# ui_front.net
KiCad netlist of a schematic drawn in Altium Designer
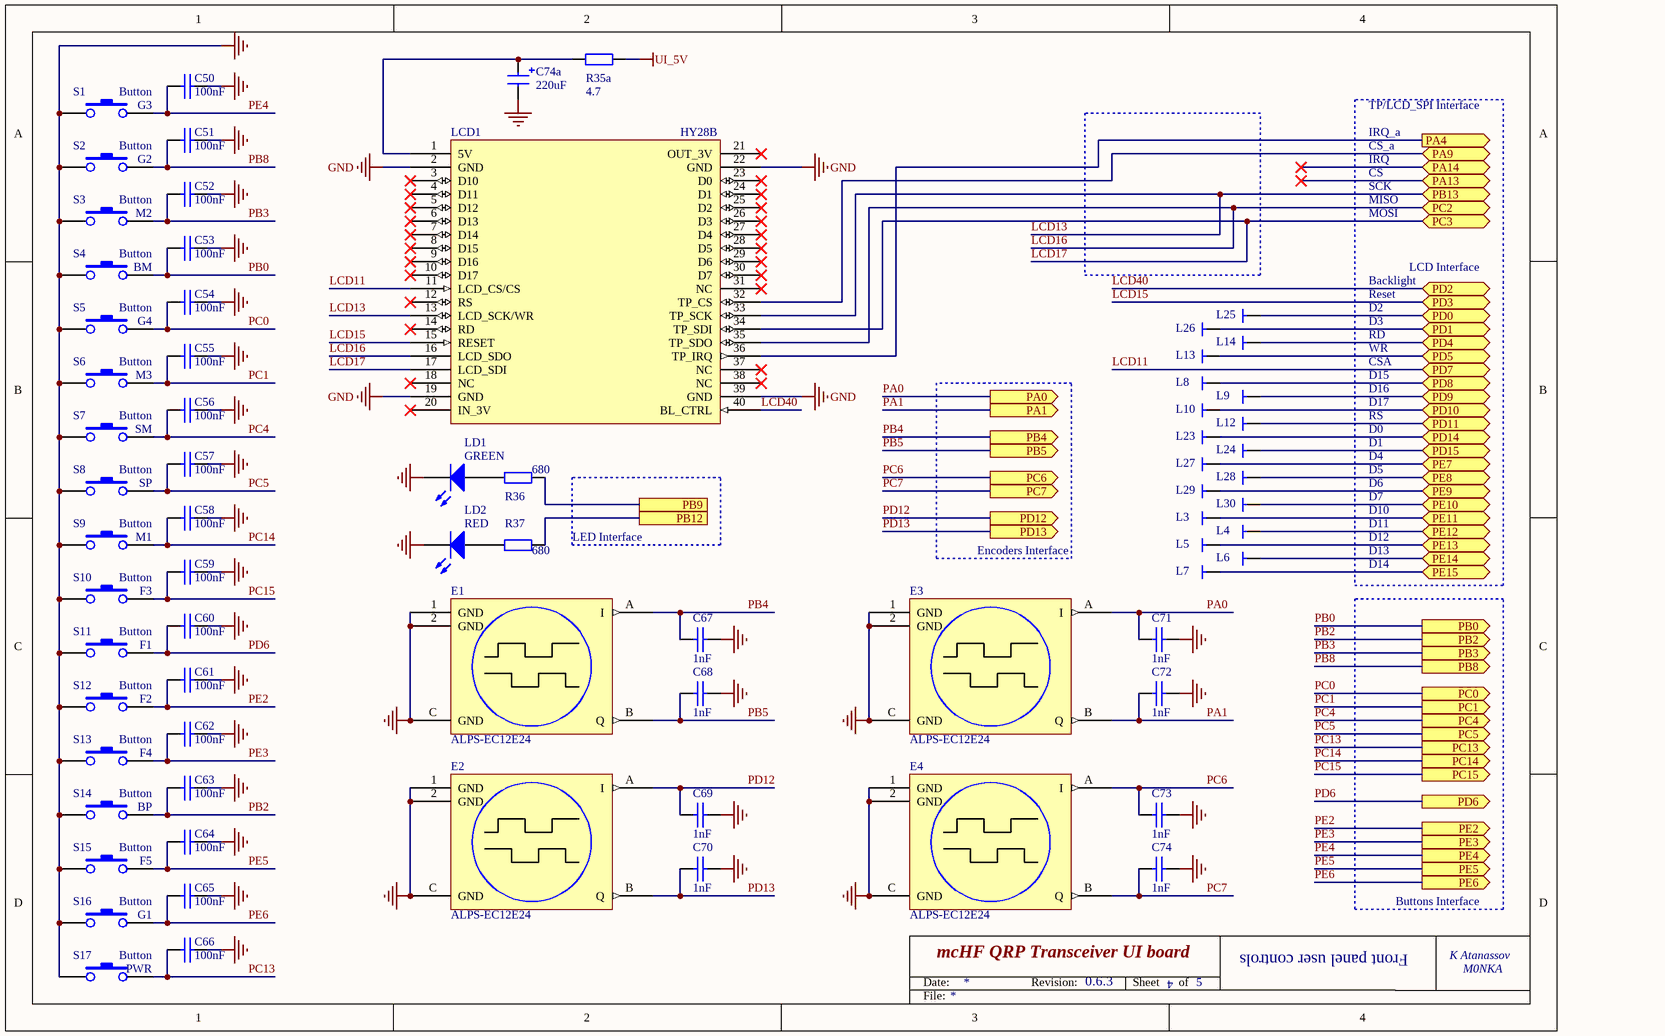
[diagram p0: ui_front.SchDoc]

(export (version "E")
  (design (tool "Eeschema 10.0.6"))
  (components
    (comp (ref "C50")
      (value "100nF")
      (footprint "0805-Pro")
      (description "Capacitor")
      (libsource (lib "mcHF_ui") (part "CAP"))
    )
    (comp (ref "C51")
      (value "100nF")
      (footprint "0805-Pro")
      (description "Capacitor")
      (libsource (lib "mcHF_ui") (part "CAP"))
    )
    (comp (ref "C52")
      (value "100nF")
      (footprint "0805-Pro")
      (description "Capacitor")
      (libsource (lib "mcHF_ui") (part "CAP"))
    )
    (comp (ref "C53")
      (value "100nF")
      (footprint "0805-Pro")
      (description "Capacitor")
      (libsource (lib "mcHF_ui") (part "CAP"))
    )
    (comp (ref "C54")
      (value "100nF")
      (footprint "0805-Pro")
      (description "Capacitor")
      (libsource (lib "mcHF_ui") (part "CAP"))
    )
    (comp (ref "C55")
      (value "100nF")
      (footprint "0805-Pro")
      (description "Capacitor")
      (libsource (lib "mcHF_ui") (part "CAP"))
    )
    (comp (ref "C56")
      (value "100nF")
      (footprint "0805-Pro")
      (description "Capacitor")
      (libsource (lib "mcHF_ui") (part "CAP"))
    )
    (comp (ref "C57")
      (value "100nF")
      (footprint "0805-Pro")
      (description "Capacitor")
      (libsource (lib "mcHF_ui") (part "CAP"))
    )
    (comp (ref "C58")
      (value "100nF")
      (footprint "0805-Pro")
      (description "Capacitor")
      (libsource (lib "mcHF_ui") (part "CAP"))
    )
    (comp (ref "C59")
      (value "100nF")
      (footprint "0805-Pro")
      (description "Capacitor")
      (libsource (lib "mcHF_ui") (part "CAP"))
    )
    (comp (ref "C60")
      (value "100nF")
      (footprint "0805-Pro")
      (description "Capacitor")
      (libsource (lib "mcHF_ui") (part "CAP"))
    )
    (comp (ref "C61")
      (value "100nF")
      (footprint "0805-Pro")
      (description "Capacitor")
      (libsource (lib "mcHF_ui") (part "CAP"))
    )
    (comp (ref "C62")
      (value "100nF")
      (footprint "0805-Pro")
      (description "Capacitor")
      (libsource (lib "mcHF_ui") (part "CAP"))
    )
    (comp (ref "C63")
      (value "100nF")
      (footprint "0805-Pro")
      (description "Capacitor")
      (libsource (lib "mcHF_ui") (part "CAP"))
    )
    (comp (ref "C64")
      (value "100nF")
      (footprint "0805-Pro")
      (description "Capacitor")
      (libsource (lib "mcHF_ui") (part "CAP"))
    )
    (comp (ref "C65")
      (value "100nF")
      (footprint "0805-Pro")
      (description "Capacitor")
      (libsource (lib "mcHF_ui") (part "CAP"))
    )
    (comp (ref "C66")
      (value "100nF")
      (footprint "0805-Pro")
      (description "Capacitor")
      (libsource (lib "mcHF_ui") (part "CAP"))
    )
    (comp (ref "C67")
      (value "1nF")
      (footprint "0805-Pro")
      (description "Capacitor")
      (libsource (lib "mcHF_ui") (part "CAP"))
    )
    (comp (ref "C68")
      (value "1nF")
      (footprint "0805-Pro")
      (description "Capacitor")
      (libsource (lib "mcHF_ui") (part "CAP"))
    )
    (comp (ref "C69")
      (value "1nF")
      (footprint "0805-Pro")
      (description "Capacitor")
      (libsource (lib "mcHF_ui") (part "CAP"))
    )
    (comp (ref "C70")
      (value "1nF")
      (footprint "0805-Pro")
      (description "Capacitor")
      (libsource (lib "mcHF_ui") (part "CAP"))
    )
    (comp (ref "C71")
      (value "1nF")
      (footprint "0805-Pro")
      (description "Capacitor")
      (libsource (lib "mcHF_ui") (part "CAP"))
    )
    (comp (ref "C72")
      (value "1nF")
      (footprint "0805-Pro")
      (description "Capacitor")
      (libsource (lib "mcHF_ui") (part "CAP"))
    )
    (comp (ref "C73")
      (value "1nF")
      (footprint "0805-Pro")
      (description "Capacitor")
      (libsource (lib "mcHF_ui") (part "CAP"))
    )
    (comp (ref "C74")
      (value "1nF")
      (footprint "0805-Pro")
      (description "Capacitor")
      (libsource (lib "mcHF_ui") (part "CAP"))
    )
    (comp (ref "C74a")
      (value "220uF")
      (footprint "CAP_ALUM")
      (description "Electrolitic capacitor")
      (libsource (lib "mcHF_ui") (part "CAP-POL"))
    )
    (comp (ref "E1")
      (value "ALPS-EC12E24")
      (footprint "Encoder")
      (description "ALPS Rotary Encoder")
      (libsource (lib "mcHF_ui") (part "Encoder"))
    )
    (comp (ref "E2")
      (value "ALPS-EC12E24")
      (footprint "Encoder")
      (description "ALPS Rotary Encoder")
      (libsource (lib "mcHF_ui") (part "Encoder"))
    )
    (comp (ref "E3")
      (value "ALPS-EC12E24")
      (footprint "Encoder")
      (description "ALPS Rotary Encoder")
      (libsource (lib "mcHF_ui") (part "Encoder"))
    )
    (comp (ref "E4")
      (value "ALPS-EC12E24")
      (footprint "Encoder")
      (description "ALPS Rotary Encoder")
      (libsource (lib "mcHF_ui") (part "Encoder"))
    )
    (comp (ref "L3")
      (value "TP")
      (footprint "tp")
      (description "Test point")
      (libsource (lib "mcHF_ui_b") (part "TP"))
    )
    (comp (ref "L4")
      (value "TP")
      (footprint "tp")
      (description "Test point")
      (libsource (lib "mcHF_ui_b") (part "TP"))
    )
    (comp (ref "L5")
      (value "TP")
      (footprint "tp")
      (description "Test point")
      (libsource (lib "mcHF_ui_b") (part "TP"))
    )
    (comp (ref "L6")
      (value "TP")
      (footprint "tp")
      (description "Test point")
      (libsource (lib "mcHF_ui_b") (part "TP"))
    )
    (comp (ref "L7")
      (value "TP")
      (footprint "tp")
      (description "Test point")
      (libsource (lib "mcHF_ui_b") (part "TP"))
    )
    (comp (ref "L8")
      (value "TP")
      (footprint "tp")
      (description "Test point")
      (libsource (lib "mcHF_ui_b") (part "TP"))
    )
    (comp (ref "L9")
      (value "TP")
      (footprint "tp")
      (description "Test point")
      (libsource (lib "mcHF_ui_b") (part "TP"))
    )
    (comp (ref "L10")
      (value "TP")
      (footprint "tp")
      (description "Test point")
      (libsource (lib "mcHF_ui_b") (part "TP"))
    )
    (comp (ref "L12")
      (value "TP")
      (footprint "tp")
      (description "Test point")
      (libsource (lib "mcHF_ui_b") (part "TP"))
    )
    (comp (ref "L13")
      (value "TP")
      (footprint "tp")
      (description "Test point")
      (libsource (lib "mcHF_ui_b") (part "TP"))
    )
    (comp (ref "L14")
      (value "TP")
      (footprint "tp")
      (description "Test point")
      (libsource (lib "mcHF_ui_b") (part "TP"))
    )
    (comp (ref "L23")
      (value "TP")
      (footprint "tp")
      (description "Test point")
      (libsource (lib "mcHF_ui_b") (part "TP"))
    )
    (comp (ref "L24")
      (value "TP")
      (footprint "tp")
      (description "Test point")
      (libsource (lib "mcHF_ui_b") (part "TP"))
    )
    (comp (ref "L25")
      (value "TP")
      (footprint "tp")
      (description "Test point")
      (libsource (lib "mcHF_ui_b") (part "TP"))
    )
    (comp (ref "L26")
      (value "TP")
      (footprint "tp")
      (description "Test point")
      (libsource (lib "mcHF_ui_b") (part "TP"))
    )
    (comp (ref "L27")
      (value "TP")
      (footprint "tp")
      (description "Test point")
      (libsource (lib "mcHF_ui_b") (part "TP"))
    )
    (comp (ref "L28")
      (value "TP")
      (footprint "tp")
      (description "Test point")
      (libsource (lib "mcHF_ui_b") (part "TP"))
    )
    (comp (ref "L29")
      (value "TP")
      (footprint "tp")
      (description "Test point")
      (libsource (lib "mcHF_ui_b") (part "TP"))
    )
    (comp (ref "L30")
      (value "TP")
      (footprint "tp")
      (description "Test point")
      (libsource (lib "mcHF_ui_b") (part "TP"))
    )
    (comp (ref "LCD1")
      (value "HY28B")
      (footprint "HY28A")
      (description "2.8 inch TFT LCD")
      (libsource (lib "mcHF_ui") (part "HY28AB"))
    )
    (comp (ref "LD1")
      (value "GREEN")
      (footprint "LED2n")
      (description "LED 3mm")
      (libsource (lib "mcHF_ui") (part "LED2"))
    )
    (comp (ref "LD2")
      (value "RED")
      (footprint "LED2n")
      (description "LED 3mm")
      (libsource (lib "mcHF_ui") (part "LED2"))
    )
    (comp (ref "R35a")
      (value "4.7")
      (footprint "1206")
      (description "Resistor")
      (libsource (lib "mcHF_ui") (part "RES"))
    )
    (comp (ref "R36")
      (value "680")
      (footprint "0805-Pro")
      (description "Resistor")
      (libsource (lib "") (part "RES_1"))
    )
    (comp (ref "R37")
      (value "680")
      (footprint "0805-Pro")
      (description "Resistor")
      (libsource (lib "") (part "RES_1"))
    )
    (comp (ref "S1")
      (value "Button")
      (footprint "BUTTON_SMD2")
      (description "Push Button")
      (fields (field (name "SOFTWARE FUNCTION") "G3"))
      (libsource (lib "mcHF_ui") (part "SW-PB"))
    )
    (comp (ref "S2")
      (value "Button")
      (footprint "BUTTON_SMD2")
      (description "Push Button")
      (fields (field (name "SOFTWARE FUNCTION") "G2"))
      (libsource (lib "mcHF_ui") (part "SW-PB"))
    )
    (comp (ref "S3")
      (value "Button")
      (footprint "BUTTON_SMD2")
      (description "Push Button")
      (fields (field (name "SOFTWARE FUNCTION") "M2"))
      (libsource (lib "mcHF_ui") (part "SW-PB"))
    )
    (comp (ref "S4")
      (value "Button")
      (footprint "BUTTON_SMD2")
      (description "Push Button")
      (fields (field (name "SOFTWARE FUNCTION") "BM"))
      (libsource (lib "mcHF_ui") (part "SW-PB"))
    )
    (comp (ref "S5")
      (value "Button")
      (footprint "BUTTON_SMD2")
      (description "Push Button")
      (fields (field (name "SOFTWARE FUNCTION") "G4"))
      (libsource (lib "mcHF_ui") (part "SW-PB"))
    )
    (comp (ref "S6")
      (value "Button")
      (footprint "BUTTON_SMD2")
      (description "Push Button")
      (fields (field (name "SOFTWARE FUNCTION") "M3"))
      (libsource (lib "mcHF_ui") (part "SW-PB"))
    )
    (comp (ref "S7")
      (value "Button")
      (footprint "BUTTON_SMD2")
      (description "Push Button")
      (fields (field (name "SOFTWARE FUNCTION") "SM"))
      (libsource (lib "mcHF_ui") (part "SW-PB"))
    )
    (comp (ref "S8")
      (value "Button")
      (footprint "BUTTON_SMD2")
      (description "Push Button")
      (fields (field (name "SOFTWARE FUNCTION") "SP"))
      (libsource (lib "mcHF_ui") (part "SW-PB"))
    )
    (comp (ref "S9")
      (value "Button")
      (footprint "BUTTON_SMD2")
      (description "Push Button")
      (fields (field (name "SOFTWARE FUNCTION") "M1"))
      (libsource (lib "mcHF_ui") (part "SW-PB"))
    )
    (comp (ref "S10")
      (value "Button")
      (footprint "BUTTON_SMD2")
      (description "Push Button")
      (fields (field (name "SOFTWARE FUNCTION") "F3"))
      (libsource (lib "mcHF_ui") (part "SW-PB"))
    )
    (comp (ref "S11")
      (value "Button")
      (footprint "BUTTON_SMD2")
      (description "Push Button")
      (fields (field (name "SOFTWARE FUNCTION") "F1"))
      (libsource (lib "mcHF_ui") (part "SW-PB"))
    )
    (comp (ref "S12")
      (value "Button")
      (footprint "BUTTON_SMD2")
      (description "Push Button")
      (fields (field (name "SOFTWARE FUNCTION") "F2"))
      (libsource (lib "mcHF_ui") (part "SW-PB"))
    )
    (comp (ref "S13")
      (value "Button")
      (footprint "BUTTON_SMD2")
      (description "Push Button")
      (fields (field (name "SOFTWARE FUNCTION") "F4"))
      (libsource (lib "mcHF_ui") (part "SW-PB"))
    )
    (comp (ref "S14")
      (value "Button")
      (footprint "BUTTON_SMD2")
      (description "Push Button")
      (fields (field (name "SOFTWARE FUNCTION") "BP"))
      (libsource (lib "mcHF_ui") (part "SW-PB"))
    )
    (comp (ref "S15")
      (value "Button")
      (footprint "BUTTON_SMD2")
      (description "Push Button")
      (fields (field (name "SOFTWARE FUNCTION") "F5"))
      (libsource (lib "mcHF_ui") (part "SW-PB"))
    )
    (comp (ref "S16")
      (value "Button")
      (footprint "BUTTON_SMD2")
      (description "Push Button")
      (fields (field (name "SOFTWARE FUNCTION") "G1"))
      (libsource (lib "mcHF_ui") (part "SW-PB"))
    )
    (comp (ref "S17")
      (value "Button")
      (footprint "BUTTON_SMD2")
      (description "Push Button")
      (fields (field (name "SOFTWARE FUNCTION") "PWR"))
      (libsource (lib "mcHF_ui") (part "SW-PB"))
    )
  )
  (nets
    (net (code "1") (name "/LCD11") (class "Default")
      (node (ref "LCD1") (pin "11") (pinfunction "LCD_CS/CS_11") (pintype "input"))
    )
    (net (code "2") (name "/LCD13") (class "Default")
      (node (ref "LCD1") (pin "13") (pinfunction "LCD_SCK/WR_13") (pintype "bidirectional"))
      (node (ref "LCD1") (pin "33") (pinfunction "TP_SCK_33") (pintype "bidirectional"))
    )
    (net (code "3") (name "/LCD15") (class "Default")
      (node (ref "LCD1") (pin "15") (pinfunction "RESET_15") (pintype "input"))
    )
    (net (code "4") (name "/LCD16") (class "Default")
      (node (ref "LCD1") (pin "16") (pinfunction "LCD_SDO_16") (pintype "passive"))
      (node (ref "LCD1") (pin "35") (pinfunction "TP_SDO_35") (pintype "bidirectional"))
    )
    (net (code "5") (name "/LCD17") (class "Default")
      (node (ref "LCD1") (pin "17") (pinfunction "LCD_SDI_17") (pintype "passive"))
      (node (ref "LCD1") (pin "34") (pinfunction "TP_SDI_34") (pintype "bidirectional"))
    )
    (net (code "6") (name "/LCD40") (class "Default")
      (node (ref "LCD1") (pin "40") (pinfunction "BL_CTRL_40") (pintype "input"))
    )
    (net (code "7") (name "/PA0") (class "Default")
      (node (ref "C71") (pin "1") (pinfunction "1_1") (pintype "passive"))
      (node (ref "E3") (pin "A") (pinfunction "I_A") (pintype "output"))
    )
    (net (code "8") (name "/PA1") (class "Default")
      (node (ref "C72") (pin "1") (pinfunction "1_1") (pintype "passive"))
      (node (ref "E3") (pin "B") (pinfunction "Q_B") (pintype "output"))
    )
    (net (code "9") (name "/PA4") (class "Default")
      (node (ref "LCD1") (pin "36") (pinfunction "TP_IRQ_36") (pintype "output"))
    )
    (net (code "10") (name "/PA9") (class "Default")
      (node (ref "LCD1") (pin "32") (pinfunction "TP_CS_32") (pintype "bidirectional"))
    )
    (net (code "13") (name "/PB0") (class "Default")
      (node (ref "C53") (pin "2") (pinfunction "2_2") (pintype "passive"))
      (node (ref "S4") (pin "2") (pinfunction "2_2") (pintype "passive"))
    )
    (net (code "14") (name "/PB2") (class "Default")
      (node (ref "C63") (pin "2") (pinfunction "2_2") (pintype "passive"))
      (node (ref "S14") (pin "2") (pinfunction "2_2") (pintype "passive"))
    )
    (net (code "15") (name "/PB3") (class "Default")
      (node (ref "C52") (pin "2") (pinfunction "2_2") (pintype "passive"))
      (node (ref "S3") (pin "2") (pinfunction "2_2") (pintype "passive"))
    )
    (net (code "16") (name "/PB4") (class "Default")
      (node (ref "C67") (pin "1") (pinfunction "1_1") (pintype "passive"))
      (node (ref "E1") (pin "A") (pinfunction "I_A") (pintype "output"))
    )
    (net (code "17") (name "/PB5") (class "Default")
      (node (ref "C68") (pin "1") (pinfunction "1_1") (pintype "passive"))
      (node (ref "E1") (pin "B") (pinfunction "Q_B") (pintype "output"))
    )
    (net (code "18") (name "/PB8") (class "Default")
      (node (ref "C51") (pin "2") (pinfunction "2_2") (pintype "passive"))
      (node (ref "S2") (pin "2") (pinfunction "2_2") (pintype "passive"))
    )
    (net (code "19") (name "/PB9") (class "Default")
      (node (ref "R36") (pin "2") (pinfunction "2_2") (pintype "passive"))
    )
    (net (code "20") (name "/PB12") (class "Default")
      (node (ref "R37") (pin "2") (pinfunction "2_2") (pintype "passive"))
    )
    (net (code "21") (name "/PC0") (class "Default")
      (node (ref "C54") (pin "2") (pinfunction "2_2") (pintype "passive"))
      (node (ref "S5") (pin "2") (pinfunction "2_2") (pintype "passive"))
    )
    (net (code "22") (name "/PC1") (class "Default")
      (node (ref "C55") (pin "2") (pinfunction "2_2") (pintype "passive"))
      (node (ref "S6") (pin "2") (pinfunction "2_2") (pintype "passive"))
    )
    (net (code "23") (name "/PC4") (class "Default")
      (node (ref "C56") (pin "2") (pinfunction "2_2") (pintype "passive"))
      (node (ref "S7") (pin "2") (pinfunction "2_2") (pintype "passive"))
    )
    (net (code "24") (name "/PC5") (class "Default")
      (node (ref "C57") (pin "2") (pinfunction "2_2") (pintype "passive"))
      (node (ref "S8") (pin "2") (pinfunction "2_2") (pintype "passive"))
    )
    (net (code "25") (name "/PC6") (class "Default")
      (node (ref "C73") (pin "1") (pinfunction "1_1") (pintype "passive"))
      (node (ref "E4") (pin "A") (pinfunction "I_A") (pintype "output"))
    )
    (net (code "26") (name "/PC7") (class "Default")
      (node (ref "C74") (pin "1") (pinfunction "1_1") (pintype "passive"))
      (node (ref "E4") (pin "B") (pinfunction "Q_B") (pintype "output"))
    )
    (net (code "27") (name "/PC13") (class "Default")
      (node (ref "C66") (pin "2") (pinfunction "2_2") (pintype "passive"))
      (node (ref "S17") (pin "2") (pinfunction "2_2") (pintype "passive"))
    )
    (net (code "28") (name "/PC14") (class "Default")
      (node (ref "C58") (pin "2") (pinfunction "2_2") (pintype "passive"))
      (node (ref "S9") (pin "2") (pinfunction "2_2") (pintype "passive"))
    )
    (net (code "29") (name "/PC15") (class "Default")
      (node (ref "C59") (pin "2") (pinfunction "2_2") (pintype "passive"))
      (node (ref "S10") (pin "2") (pinfunction "2_2") (pintype "passive"))
    )
    (net (code "30") (name "/PD0") (class "Default")
      (node (ref "L25") (pin "1") (pinfunction "1_1") (pintype "passive"))
    )
    (net (code "31") (name "/PD1") (class "Default")
      (node (ref "L26") (pin "1") (pinfunction "1_1") (pintype "passive"))
    )
    (net (code "32") (name "/PD4") (class "Default")
      (node (ref "L14") (pin "1") (pinfunction "1_1") (pintype "passive"))
    )
    (net (code "33") (name "/PD5") (class "Default")
      (node (ref "L13") (pin "1") (pinfunction "1_1") (pintype "passive"))
    )
    (net (code "34") (name "/PD6") (class "Default")
      (node (ref "C60") (pin "2") (pinfunction "2_2") (pintype "passive"))
      (node (ref "S11") (pin "2") (pinfunction "2_2") (pintype "passive"))
    )
    (net (code "35") (name "/PD8") (class "Default")
      (node (ref "L8") (pin "1") (pinfunction "1_1") (pintype "passive"))
    )
    (net (code "36") (name "/PD9") (class "Default")
      (node (ref "L9") (pin "1") (pinfunction "1_1") (pintype "passive"))
    )
    (net (code "37") (name "/PD10") (class "Default")
      (node (ref "L10") (pin "1") (pinfunction "1_1") (pintype "passive"))
    )
    (net (code "38") (name "/PD11") (class "Default")
      (node (ref "L12") (pin "1") (pinfunction "1_1") (pintype "passive"))
    )
    (net (code "39") (name "/PD12") (class "Default")
      (node (ref "C69") (pin "1") (pinfunction "1_1") (pintype "passive"))
      (node (ref "E2") (pin "A") (pinfunction "I_A") (pintype "output"))
    )
    (net (code "40") (name "/PD13") (class "Default")
      (node (ref "C70") (pin "1") (pinfunction "1_1") (pintype "passive"))
      (node (ref "E2") (pin "B") (pinfunction "Q_B") (pintype "output"))
    )
    (net (code "41") (name "/PD14") (class "Default")
      (node (ref "L23") (pin "1") (pinfunction "1_1") (pintype "passive"))
    )
    (net (code "42") (name "/PD15") (class "Default")
      (node (ref "L24") (pin "1") (pinfunction "1_1") (pintype "passive"))
    )
    (net (code "43") (name "/PE2") (class "Default")
      (node (ref "C61") (pin "2") (pinfunction "2_2") (pintype "passive"))
      (node (ref "S12") (pin "2") (pinfunction "2_2") (pintype "passive"))
    )
    (net (code "44") (name "/PE3") (class "Default")
      (node (ref "C62") (pin "2") (pinfunction "2_2") (pintype "passive"))
      (node (ref "S13") (pin "2") (pinfunction "2_2") (pintype "passive"))
    )
    (net (code "45") (name "/PE4") (class "Default")
      (node (ref "C50") (pin "2") (pinfunction "2_2") (pintype "passive"))
      (node (ref "S1") (pin "2") (pinfunction "2_2") (pintype "passive"))
    )
    (net (code "46") (name "/PE5") (class "Default")
      (node (ref "C64") (pin "2") (pinfunction "2_2") (pintype "passive"))
      (node (ref "S15") (pin "2") (pinfunction "2_2") (pintype "passive"))
    )
    (net (code "47") (name "/PE6") (class "Default")
      (node (ref "C65") (pin "2") (pinfunction "2_2") (pintype "passive"))
      (node (ref "S16") (pin "2") (pinfunction "2_2") (pintype "passive"))
    )
    (net (code "48") (name "/PE7") (class "Default")
      (node (ref "L27") (pin "1") (pinfunction "1_1") (pintype "passive"))
    )
    (net (code "49") (name "/PE8") (class "Default")
      (node (ref "L28") (pin "1") (pinfunction "1_1") (pintype "passive"))
    )
    (net (code "50") (name "/PE9") (class "Default")
      (node (ref "L29") (pin "1") (pinfunction "1_1") (pintype "passive"))
    )
    (net (code "51") (name "/PE10") (class "Default")
      (node (ref "L30") (pin "1") (pinfunction "1_1") (pintype "passive"))
    )
    (net (code "52") (name "/PE11") (class "Default")
      (node (ref "L3") (pin "1") (pinfunction "1_1") (pintype "passive"))
    )
    (net (code "53") (name "/PE12") (class "Default")
      (node (ref "L4") (pin "1") (pinfunction "1_1") (pintype "passive"))
    )
    (net (code "54") (name "/PE13") (class "Default")
      (node (ref "L5") (pin "1") (pinfunction "1_1") (pintype "passive"))
    )
    (net (code "55") (name "/PE14") (class "Default")
      (node (ref "L6") (pin "1") (pinfunction "1_1") (pintype "passive"))
    )
    (net (code "56") (name "/PE15") (class "Default")
      (node (ref "L7") (pin "1") (pinfunction "1_1") (pintype "passive"))
    )
    (net (code "57") (name "GND") (class "Default")
      (node (ref "C50") (pin "1") (pinfunction "1_1") (pintype "passive"))
      (node (ref "C51") (pin "1") (pinfunction "1_1") (pintype "passive"))
      (node (ref "C52") (pin "1") (pinfunction "1_1") (pintype "passive"))
      (node (ref "C53") (pin "1") (pinfunction "1_1") (pintype "passive"))
      (node (ref "C54") (pin "1") (pinfunction "1_1") (pintype "passive"))
      (node (ref "C55") (pin "1") (pinfunction "1_1") (pintype "passive"))
      (node (ref "C56") (pin "1") (pinfunction "1_1") (pintype "passive"))
      (node (ref "C57") (pin "1") (pinfunction "1_1") (pintype "passive"))
      (node (ref "C58") (pin "1") (pinfunction "1_1") (pintype "passive"))
      (node (ref "C59") (pin "1") (pinfunction "1_1") (pintype "passive"))
      (node (ref "C60") (pin "1") (pinfunction "1_1") (pintype "passive"))
      (node (ref "C61") (pin "1") (pinfunction "1_1") (pintype "passive"))
      (node (ref "C62") (pin "1") (pinfunction "1_1") (pintype "passive"))
      (node (ref "C63") (pin "1") (pinfunction "1_1") (pintype "passive"))
      (node (ref "C64") (pin "1") (pinfunction "1_1") (pintype "passive"))
      (node (ref "C65") (pin "1") (pinfunction "1_1") (pintype "passive"))
      (node (ref "C66") (pin "1") (pinfunction "1_1") (pintype "passive"))
      (node (ref "C67") (pin "2") (pinfunction "2_2") (pintype "passive"))
      (node (ref "C68") (pin "2") (pinfunction "2_2") (pintype "passive"))
      (node (ref "C69") (pin "2") (pinfunction "2_2") (pintype "passive"))
      (node (ref "C70") (pin "2") (pinfunction "2_2") (pintype "passive"))
      (node (ref "C71") (pin "2") (pinfunction "2_2") (pintype "passive"))
      (node (ref "C72") (pin "2") (pinfunction "2_2") (pintype "passive"))
      (node (ref "C73") (pin "2") (pinfunction "2_2") (pintype "passive"))
      (node (ref "C74") (pin "2") (pinfunction "2_2") (pintype "passive"))
      (node (ref "C74a") (pin "2") (pinfunction "2_2") (pintype "passive"))
      (node (ref "E1") (pin "1") (pinfunction "GND_1") (pintype "power_in"))
      (node (ref "E1") (pin "2") (pinfunction "GND_2") (pintype "power_in"))
      (node (ref "E1") (pin "C") (pinfunction "GND_C") (pintype "power_in"))
      (node (ref "E2") (pin "1") (pinfunction "GND_1") (pintype "power_in"))
      (node (ref "E2") (pin "2") (pinfunction "GND_2") (pintype "power_in"))
      (node (ref "E2") (pin "C") (pinfunction "GND_C") (pintype "power_in"))
      (node (ref "E3") (pin "1") (pinfunction "GND_1") (pintype "power_in"))
      (node (ref "E3") (pin "2") (pinfunction "GND_2") (pintype "power_in"))
      (node (ref "E3") (pin "C") (pinfunction "GND_C") (pintype "power_in"))
      (node (ref "E4") (pin "1") (pinfunction "GND_1") (pintype "power_in"))
      (node (ref "E4") (pin "2") (pinfunction "GND_2") (pintype "power_in"))
      (node (ref "E4") (pin "C") (pinfunction "GND_C") (pintype "power_in"))
      (node (ref "LCD1") (pin "19") (pinfunction "GND_19") (pintype "power_in"))
      (node (ref "LCD1") (pin "2") (pinfunction "GND_2") (pintype "power_in"))
      (node (ref "LCD1") (pin "22") (pinfunction "GND_22") (pintype "power_in"))
      (node (ref "LCD1") (pin "39") (pinfunction "GND_39") (pintype "power_in"))
      (node (ref "LD1") (pin "2") (pinfunction "K_2") (pintype "passive"))
      (node (ref "LD2") (pin "2") (pinfunction "K_2") (pintype "passive"))
      (node (ref "S1") (pin "1") (pinfunction "1_1") (pintype "passive"))
      (node (ref "S10") (pin "1") (pinfunction "1_1") (pintype "passive"))
      (node (ref "S11") (pin "1") (pinfunction "1_1") (pintype "passive"))
      (node (ref "S12") (pin "1") (pinfunction "1_1") (pintype "passive"))
      (node (ref "S13") (pin "1") (pinfunction "1_1") (pintype "passive"))
      (node (ref "S14") (pin "1") (pinfunction "1_1") (pintype "passive"))
      (node (ref "S15") (pin "1") (pinfunction "1_1") (pintype "passive"))
      (node (ref "S16") (pin "1") (pinfunction "1_1") (pintype "passive"))
      (node (ref "S17") (pin "1") (pinfunction "1_1") (pintype "passive"))
      (node (ref "S2") (pin "1") (pinfunction "1_1") (pintype "passive"))
      (node (ref "S3") (pin "1") (pinfunction "1_1") (pintype "passive"))
      (node (ref "S4") (pin "1") (pinfunction "1_1") (pintype "passive"))
      (node (ref "S5") (pin "1") (pinfunction "1_1") (pintype "passive"))
      (node (ref "S6") (pin "1") (pinfunction "1_1") (pintype "passive"))
      (node (ref "S7") (pin "1") (pinfunction "1_1") (pintype "passive"))
      (node (ref "S8") (pin "1") (pinfunction "1_1") (pintype "passive"))
      (node (ref "S9") (pin "1") (pinfunction "1_1") (pintype "passive"))
    )
    (net (code "58") (name "Net-(LCD1-5V)") (class "Default")
      (node (ref "C74a") (pin "1") (pinfunction "1_1") (pintype "passive"))
      (node (ref "LCD1") (pin "1") (pinfunction "5V_1") (pintype "power_in"))
      (node (ref "R35a") (pin "2") (pinfunction "2_2") (pintype "passive"))
    )
    (net (code "59") (name "Net-(LD1-A)") (class "Default")
      (node (ref "LD1") (pin "1") (pinfunction "A_1") (pintype "passive"))
      (node (ref "R36") (pin "1") (pinfunction "1_1") (pintype "passive"))
    )
    (net (code "60") (name "Net-(LD2-A)") (class "Default")
      (node (ref "LD2") (pin "1") (pinfunction "A_1") (pintype "passive"))
      (node (ref "R37") (pin "1") (pinfunction "1_1") (pintype "passive"))
    )
    (net (code "61") (name "UI_5V") (class "Default")
      (node (ref "R35a") (pin "1") (pinfunction "1_1") (pintype "passive"))
    )
    (net (code "62") (name "unconnected-(LCD1-D0-Pad23)") (class "Default")
      (node (ref "LCD1") (pin "23") (pinfunction "D0_23") (pintype "bidirectional+no_connect"))
    )
    (net (code "63") (name "unconnected-(LCD1-D1-Pad24)") (class "Default")
      (node (ref "LCD1") (pin "24") (pinfunction "D1_24") (pintype "bidirectional+no_connect"))
    )
    (net (code "64") (name "unconnected-(LCD1-D2-Pad25)") (class "Default")
      (node (ref "LCD1") (pin "25") (pinfunction "D2_25") (pintype "bidirectional+no_connect"))
    )
    (net (code "65") (name "unconnected-(LCD1-D3-Pad26)") (class "Default")
      (node (ref "LCD1") (pin "26") (pinfunction "D3_26") (pintype "bidirectional+no_connect"))
    )
    (net (code "66") (name "unconnected-(LCD1-D4-Pad27)") (class "Default")
      (node (ref "LCD1") (pin "27") (pinfunction "D4_27") (pintype "bidirectional+no_connect"))
    )
    (net (code "67") (name "unconnected-(LCD1-D5-Pad28)") (class "Default")
      (node (ref "LCD1") (pin "28") (pinfunction "D5_28") (pintype "bidirectional+no_connect"))
    )
    (net (code "68") (name "unconnected-(LCD1-D6-Pad29)") (class "Default")
      (node (ref "LCD1") (pin "29") (pinfunction "D6_29") (pintype "bidirectional+no_connect"))
    )
    (net (code "69") (name "unconnected-(LCD1-D7-Pad30)") (class "Default")
      (node (ref "LCD1") (pin "30") (pinfunction "D7_30") (pintype "bidirectional+no_connect"))
    )
    (net (code "70") (name "unconnected-(LCD1-D10-Pad3)") (class "Default")
      (node (ref "LCD1") (pin "3") (pinfunction "D10_3") (pintype "bidirectional+no_connect"))
    )
    (net (code "71") (name "unconnected-(LCD1-D11-Pad4)") (class "Default")
      (node (ref "LCD1") (pin "4") (pinfunction "D11_4") (pintype "bidirectional+no_connect"))
    )
    (net (code "72") (name "unconnected-(LCD1-D12-Pad5)") (class "Default")
      (node (ref "LCD1") (pin "5") (pinfunction "D12_5") (pintype "bidirectional+no_connect"))
    )
    (net (code "73") (name "unconnected-(LCD1-D13-Pad6)") (class "Default")
      (node (ref "LCD1") (pin "6") (pinfunction "D13_6") (pintype "bidirectional+no_connect"))
    )
    (net (code "74") (name "unconnected-(LCD1-D14-Pad7)") (class "Default")
      (node (ref "LCD1") (pin "7") (pinfunction "D14_7") (pintype "bidirectional+no_connect"))
    )
    (net (code "75") (name "unconnected-(LCD1-D15-Pad8)") (class "Default")
      (node (ref "LCD1") (pin "8") (pinfunction "D15_8") (pintype "bidirectional+no_connect"))
    )
    (net (code "76") (name "unconnected-(LCD1-D16-Pad9)") (class "Default")
      (node (ref "LCD1") (pin "9") (pinfunction "D16_9") (pintype "bidirectional+no_connect"))
    )
    (net (code "77") (name "unconnected-(LCD1-D17-Pad10)") (class "Default")
      (node (ref "LCD1") (pin "10") (pinfunction "D17_10") (pintype "bidirectional+no_connect"))
    )
    (net (code "78") (name "unconnected-(LCD1-IN_3V-Pad20)") (class "Default")
      (node (ref "LCD1") (pin "20") (pinfunction "IN_3V_20") (pintype "power_in+no_connect"))
    )
    (net (code "79") (name "unconnected-(LCD1-NC-Pad18)") (class "Default")
      (node (ref "LCD1") (pin "18") (pinfunction "NC_18") (pintype "passive+no_connect"))
    )
    (net (code "80") (name "unconnected-(LCD1-NC-Pad31)") (class "Default")
      (node (ref "LCD1") (pin "31") (pinfunction "NC_31") (pintype "passive+no_connect"))
    )
    (net (code "81") (name "unconnected-(LCD1-NC-Pad37)") (class "Default")
      (node (ref "LCD1") (pin "37") (pinfunction "NC_37") (pintype "passive+no_connect"))
    )
    (net (code "82") (name "unconnected-(LCD1-NC-Pad38)") (class "Default")
      (node (ref "LCD1") (pin "38") (pinfunction "NC_38") (pintype "passive+no_connect"))
    )
    (net (code "83") (name "unconnected-(LCD1-OUT_3V-Pad21)") (class "Default")
      (node (ref "LCD1") (pin "21") (pinfunction "OUT_3V_21") (pintype "power_in+no_connect"))
    )
    (net (code "84") (name "unconnected-(LCD1-RD-Pad14)") (class "Default")
      (node (ref "LCD1") (pin "14") (pinfunction "RD_14") (pintype "bidirectional+no_connect"))
    )
    (net (code "85") (name "unconnected-(LCD1-RS-Pad12)") (class "Default")
      (node (ref "LCD1") (pin "12") (pinfunction "RS_12") (pintype "bidirectional+no_connect"))
    )
  )
)
